# STMConnector.net
KiCad netlist of a schematic drawn in EAGLE
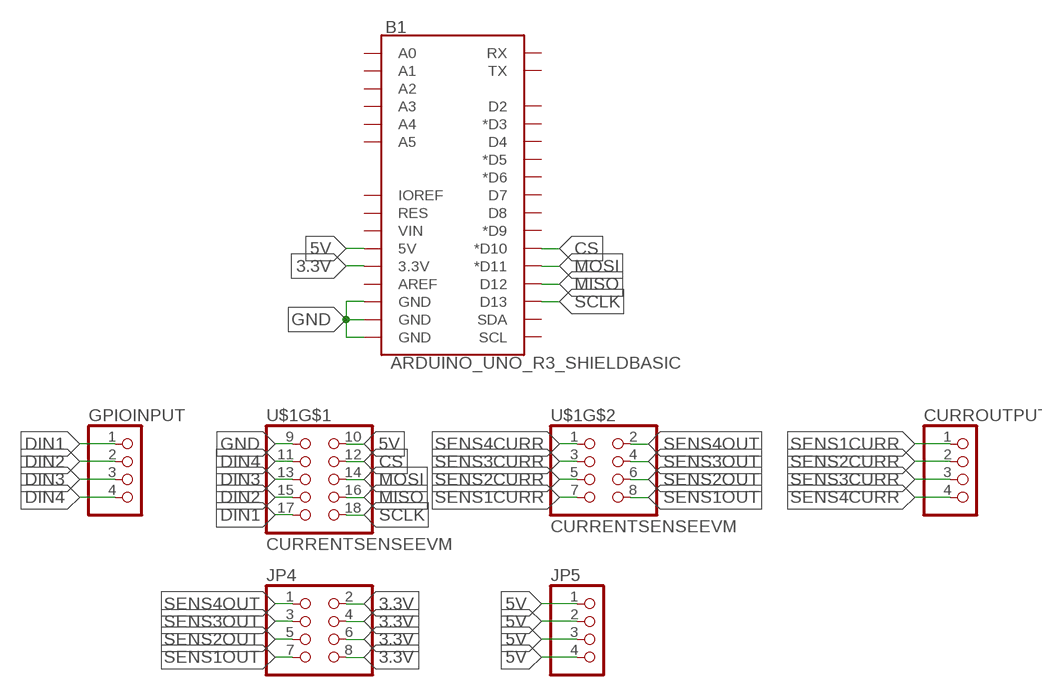
[diagram p0: schematic, sheet 1]

(export (version "E")
  (design (tool "Eeschema 10.0.6"))
  (components
    (comp (ref "B1")
      (value "ARDUINO_UNO_R3_SHIELDBASIC")
      (footprint "eagle-import:UNO_R3_SHIELD")
      (libsource (lib "eagle-import") (part "ARDUINO_UNO_R3_SHIELDBASIC"))
    )
    (comp (ref "CURROUTPUT")
      (value "PINHD-1X4")
      (footprint "eagle-import:1X04")
      (libsource (lib "eagle-import") (part "PINHD-1X4"))
    )
    (comp (ref "GPIOINPUT")
      (value "PINHD-1X4")
      (footprint "eagle-import:1X04")
      (libsource (lib "eagle-import") (part "PINHD-1X4"))
    )
    (comp (ref "JP4")
      (value "PINHD-2X4")
      (footprint "eagle-import:2X04")
      (libsource (lib "eagle-import") (part "PINHD-2X4"))
    )
    (comp (ref "JP5")
      (value "PINHD-1X4")
      (footprint "eagle-import:1X04")
      (libsource (lib "eagle-import") (part "PINHD-1X4"))
    )
    (comp (ref "U$1")
      (value "CURRENTSENSEEVM")
      (footprint "eagle-import:CURRENTSENSEEVM")
      (libsource (lib "eagle-import") (part "CURRENTSENSEEVM"))
    )
  )
  (nets
    (net (code "1") (name "3.3V") (class "Default")
      (node (ref "B1") (pin "3.3V") (pinfunction "3.3V_3.3V") (pintype "bidirectional"))
      (node (ref "JP4") (pin "2") (pinfunction "2_2") (pintype "passive"))
      (node (ref "JP4") (pin "4") (pinfunction "4_4") (pintype "passive"))
      (node (ref "JP4") (pin "6") (pinfunction "6_6") (pintype "passive"))
      (node (ref "JP4") (pin "8") (pinfunction "8_8") (pintype "passive"))
    )
    (net (code "2") (name "5V") (class "Default")
      (node (ref "B1") (pin "5V") (pinfunction "5V_5V") (pintype "bidirectional"))
      (node (ref "JP5") (pin "1") (pinfunction "1_1") (pintype "passive"))
      (node (ref "JP5") (pin "2") (pinfunction "2_2") (pintype "passive"))
      (node (ref "JP5") (pin "3") (pinfunction "3_3") (pintype "passive"))
      (node (ref "JP5") (pin "4") (pinfunction "4_4") (pintype "passive"))
      (node (ref "U$1") (pin "10") (pinfunction "2_10") (pintype "passive"))
    )
    (net (code "3") (name "CS") (class "Default")
      (node (ref "B1") (pin "D10") (pinfunction "*D10_D10") (pintype "bidirectional"))
      (node (ref "U$1") (pin "12") (pinfunction "4_12") (pintype "passive"))
    )
    (net (code "4") (name "DIN1") (class "Default")
      (node (ref "GPIOINPUT") (pin "1") (pinfunction "1_1") (pintype "passive"))
      (node (ref "U$1") (pin "17") (pinfunction "9_17") (pintype "passive"))
    )
    (net (code "5") (name "DIN2") (class "Default")
      (node (ref "GPIOINPUT") (pin "2") (pinfunction "2_2") (pintype "passive"))
      (node (ref "U$1") (pin "15") (pinfunction "7_15") (pintype "passive"))
    )
    (net (code "6") (name "DIN3") (class "Default")
      (node (ref "GPIOINPUT") (pin "3") (pinfunction "3_3") (pintype "passive"))
      (node (ref "U$1") (pin "13") (pinfunction "5_13") (pintype "passive"))
    )
    (net (code "7") (name "DIN4") (class "Default")
      (node (ref "GPIOINPUT") (pin "4") (pinfunction "4_4") (pintype "passive"))
      (node (ref "U$1") (pin "11") (pinfunction "3_11") (pintype "passive"))
    )
    (net (code "8") (name "GND") (class "Default")
      (node (ref "B1") (pin "GND@0") (pinfunction "GND_GND@0") (pintype "bidirectional"))
      (node (ref "B1") (pin "GND@1") (pinfunction "GND_GND@1") (pintype "bidirectional"))
      (node (ref "B1") (pin "GND@2") (pinfunction "GND_GND@2") (pintype "bidirectional"))
      (node (ref "U$1") (pin "9") (pinfunction "1_9") (pintype "passive"))
    )
    (net (code "9") (name "MISO") (class "Default")
      (node (ref "B1") (pin "D12") (pinfunction "D12_D12") (pintype "bidirectional"))
      (node (ref "U$1") (pin "16") (pinfunction "8_16") (pintype "passive"))
    )
    (net (code "10") (name "MOSI") (class "Default")
      (node (ref "B1") (pin "D11") (pinfunction "*D11_D11") (pintype "bidirectional"))
      (node (ref "U$1") (pin "14") (pinfunction "6_14") (pintype "passive"))
    )
    (net (code "11") (name "SCLK") (class "Default")
      (node (ref "B1") (pin "D13") (pinfunction "D13_D13") (pintype "bidirectional"))
      (node (ref "U$1") (pin "18") (pinfunction "10_18") (pintype "passive"))
    )
    (net (code "12") (name "SENS1CURR") (class "Default")
      (node (ref "CURROUTPUT") (pin "1") (pinfunction "1_1") (pintype "passive"))
      (node (ref "U$1") (pin "7") (pinfunction "7_7") (pintype "passive"))
    )
    (net (code "13") (name "SENS1OUT") (class "Default")
      (node (ref "JP4") (pin "7") (pinfunction "7_7") (pintype "passive"))
      (node (ref "U$1") (pin "8") (pinfunction "8_8") (pintype "passive"))
    )
    (net (code "14") (name "SENS2CURR") (class "Default")
      (node (ref "CURROUTPUT") (pin "2") (pinfunction "2_2") (pintype "passive"))
      (node (ref "U$1") (pin "5") (pinfunction "5_5") (pintype "passive"))
    )
    (net (code "15") (name "SENS2OUT") (class "Default")
      (node (ref "JP4") (pin "5") (pinfunction "5_5") (pintype "passive"))
      (node (ref "U$1") (pin "6") (pinfunction "6_6") (pintype "passive"))
    )
    (net (code "16") (name "SENS3CURR") (class "Default")
      (node (ref "CURROUTPUT") (pin "3") (pinfunction "3_3") (pintype "passive"))
      (node (ref "U$1") (pin "3") (pinfunction "3_3") (pintype "passive"))
    )
    (net (code "17") (name "SENS3OUT") (class "Default")
      (node (ref "JP4") (pin "3") (pinfunction "3_3") (pintype "passive"))
      (node (ref "U$1") (pin "4") (pinfunction "4_4") (pintype "passive"))
    )
    (net (code "18") (name "SENS4CURR") (class "Default")
      (node (ref "CURROUTPUT") (pin "4") (pinfunction "4_4") (pintype "passive"))
      (node (ref "U$1") (pin "1") (pinfunction "1_1") (pintype "passive"))
    )
    (net (code "19") (name "SENS4OUT") (class "Default")
      (node (ref "JP4") (pin "1") (pinfunction "1_1") (pintype "passive"))
      (node (ref "U$1") (pin "2") (pinfunction "2_2") (pintype "passive"))
    )
    (net (code "20") (name "unconnected-(B1-*D3-PadD3)") (class "Default")
      (node (ref "B1") (pin "D3") (pinfunction "*D3_D3") (pintype "bidirectional"))
    )
    (net (code "21") (name "unconnected-(B1-*D5-PadD5)") (class "Default")
      (node (ref "B1") (pin "D5") (pinfunction "*D5_D5") (pintype "bidirectional"))
    )
    (net (code "22") (name "unconnected-(B1-*D6-PadD6)") (class "Default")
      (node (ref "B1") (pin "D6") (pinfunction "*D6_D6") (pintype "bidirectional"))
    )
    (net (code "23") (name "unconnected-(B1-*D9-PadD9)") (class "Default")
      (node (ref "B1") (pin "D9") (pinfunction "*D9_D9") (pintype "bidirectional"))
    )
    (net (code "24") (name "unconnected-(B1-PadA0)") (class "Default")
      (node (ref "B1") (pin "A0") (pinfunction "A0_A0") (pintype "bidirectional"))
    )
    (net (code "25") (name "unconnected-(B1-PadA1)") (class "Default")
      (node (ref "B1") (pin "A1") (pinfunction "A1_A1") (pintype "bidirectional"))
    )
    (net (code "26") (name "unconnected-(B1-PadA2)") (class "Default")
      (node (ref "B1") (pin "A2") (pinfunction "A2_A2") (pintype "bidirectional"))
    )
    (net (code "27") (name "unconnected-(B1-PadA3)") (class "Default")
      (node (ref "B1") (pin "A3") (pinfunction "A3_A3") (pintype "bidirectional"))
    )
    (net (code "28") (name "unconnected-(B1-PadA4)") (class "Default")
      (node (ref "B1") (pin "A4") (pinfunction "A4_A4") (pintype "bidirectional"))
    )
    (net (code "29") (name "unconnected-(B1-PadA5)") (class "Default")
      (node (ref "B1") (pin "A5") (pinfunction "A5_A5") (pintype "bidirectional"))
    )
    (net (code "30") (name "unconnected-(B1-PadAREF)") (class "Default")
      (node (ref "B1") (pin "AREF") (pinfunction "AREF_AREF") (pintype "bidirectional"))
    )
    (net (code "31") (name "unconnected-(B1-PadD2)") (class "Default")
      (node (ref "B1") (pin "D2") (pinfunction "D2_D2") (pintype "bidirectional"))
    )
    (net (code "32") (name "unconnected-(B1-PadD4)") (class "Default")
      (node (ref "B1") (pin "D4") (pinfunction "D4_D4") (pintype "bidirectional"))
    )
    (net (code "33") (name "unconnected-(B1-PadD7)") (class "Default")
      (node (ref "B1") (pin "D7") (pinfunction "D7_D7") (pintype "bidirectional"))
    )
    (net (code "34") (name "unconnected-(B1-PadD8)") (class "Default")
      (node (ref "B1") (pin "D8") (pinfunction "D8_D8") (pintype "bidirectional"))
    )
    (net (code "35") (name "unconnected-(B1-PadIOREF)") (class "Default")
      (node (ref "B1") (pin "IOREF") (pinfunction "IOREF_IOREF") (pintype "bidirectional"))
    )
    (net (code "36") (name "unconnected-(B1-PadRES)") (class "Default")
      (node (ref "B1") (pin "RES") (pinfunction "RES_RES") (pintype "bidirectional"))
    )
    (net (code "37") (name "unconnected-(B1-PadRX)") (class "Default")
      (node (ref "B1") (pin "RX") (pinfunction "RX_RX") (pintype "bidirectional"))
    )
    (net (code "38") (name "unconnected-(B1-PadSCL)") (class "Default")
      (node (ref "B1") (pin "SCL") (pinfunction "SCL_SCL") (pintype "bidirectional"))
    )
    (net (code "39") (name "unconnected-(B1-PadSDA)") (class "Default")
      (node (ref "B1") (pin "SDA") (pinfunction "SDA_SDA") (pintype "bidirectional"))
    )
    (net (code "40") (name "unconnected-(B1-PadTX)") (class "Default")
      (node (ref "B1") (pin "TX") (pinfunction "TX_TX") (pintype "bidirectional"))
    )
    (net (code "41") (name "unconnected-(B1-PadVIN)") (class "Default")
      (node (ref "B1") (pin "VIN") (pinfunction "VIN_VIN") (pintype "bidirectional"))
    )
  )
)
